# Button.net
KiCad netlist of a schematic drawn in Altium Designer
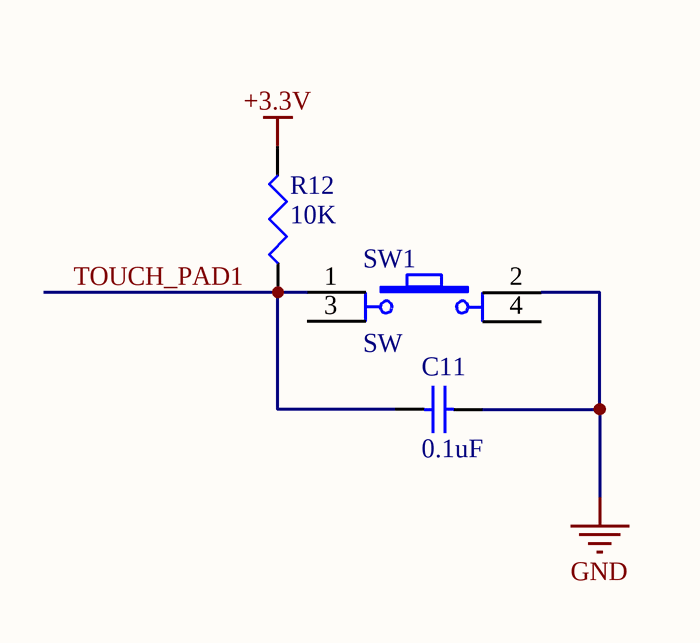
[diagram p0: Button.SchDoc]

(export (version "E")
  (design (tool "Eeschema 10.0.6"))
  (components
    (comp (ref "C11")
      (value "0.1uF")
      (footprint "C0603")
      (description "Capacitor (Semiconductor SIM Model)")
      (fields (field (name "PUBLISHER") "Altium Limited"))
      (libsource (lib "VNSKILLS2014-ASM") (part "Cap Semi"))
    )
    (comp (ref "R12")
      (value "10K")
      (footprint "J1-0603")
      (description "Resistor")
      (fields (field (name "PUBLISHER") "Altium Limited"))
      (libsource (lib "Miscellaneous Devices") (part "Res3"))
    )
    (comp (ref "SW1")
      (value "SW")
      (footprint "SW4")
      (description "Switch button 4 pin")
      (libsource (lib "syhaunguyen") (part "SW4"))
    )
  )
  (nets
    (net (code "1") (name "+3.3V") (class "Default")
      (node (ref "R12") (pin "2") (pinfunction "2_2") (pintype "passive"))
    )
    (net (code "2") (name "/TOUCH_PAD1") (class "Default")
      (node (ref "C11") (pin "2") (pinfunction "2_2") (pintype "passive"))
      (node (ref "R12") (pin "1") (pinfunction "1_1") (pintype "passive"))
      (node (ref "SW1") (pin "1") (pintype "passive"))
    )
    (net (code "3") (name "GND") (class "Default")
      (node (ref "C11") (pin "1") (pinfunction "1_1") (pintype "passive"))
      (node (ref "SW1") (pin "2") (pintype "passive"))
    )
    (net (code "4") (name "unconnected-(SW1-Pad3)") (class "Default")
      (node (ref "SW1") (pin "3") (pintype "passive"))
    )
    (net (code "5") (name "unconnected-(SW1-Pad4)") (class "Default")
      (node (ref "SW1") (pin "4") (pintype "passive"))
    )
  )
)
